# sel-driver.net
KiCad netlist of a schematic drawn in EAGLE
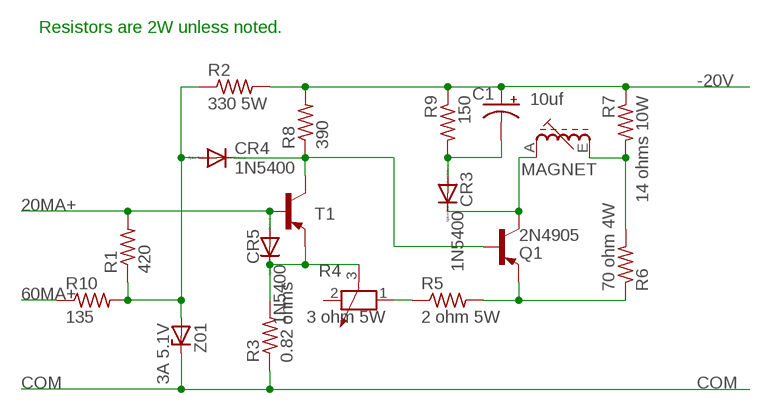
[diagram p0: schematic, sheet 1]

(export (version "E")
  (design (tool "Eeschema 10.0.6"))
  (components
    (comp (ref "C1")
      (value "10uf")
      (footprint "eagle-import:153CLV-1010")
      (libsource (lib "eagle-import") (part "CPOL-US153CLV-1010"))
    )
    (comp (ref "CR3")
      (value "1N5400")
      (footprint "eagle-import:DO201-15")
      (libsource (lib "eagle-import") (part "1N5400"))
    )
    (comp (ref "CR4")
      (value "1N5400")
      (footprint "eagle-import:DO201-15")
      (libsource (lib "eagle-import") (part "1N5400"))
    )
    (comp (ref "CR5")
      (value "1N5400")
      (footprint "eagle-import:DO201-15")
      (libsource (lib "eagle-import") (part "1N5400"))
    )
    (comp (ref "MAGNET")
      (value "71E")
      (footprint "eagle-import:71E")
      (libsource (lib "eagle-import") (part "71E"))
    )
    (comp (ref "Q1")
      (value "2N4905")
      (footprint "eagle-import:TO3")
      (libsource (lib "eagle-import") (part "2N4905"))
    )
    (comp (ref "R1")
      (value "420")
      (footprint "eagle-import:0922_22")
      (libsource (lib "eagle-import") (part "R-US_0922/22"))
    )
    (comp (ref "R2")
      (value "330 5W")
      (footprint "eagle-import:0922_22")
      (libsource (lib "eagle-import") (part "R-US_0922/22"))
    )
    (comp (ref "R3")
      (value "0.82 ohms")
      (footprint "eagle-import:0922_22")
      (libsource (lib "eagle-import") (part "R-US_0922/22"))
    )
    (comp (ref "R4")
      (value "3 ohm 5W")
      (footprint "eagle-import:PT-10")
      (libsource (lib "eagle-import") (part "POTENTIOMETER_PT-10"))
    )
    (comp (ref "R5")
      (value "2 ohm 5W")
      (footprint "eagle-import:0922_22")
      (libsource (lib "eagle-import") (part "R-US_0922/22"))
    )
    (comp (ref "R6")
      (value "70 ohm 4W")
      (footprint "eagle-import:0922_22")
      (libsource (lib "eagle-import") (part "R-US_0922/22"))
    )
    (comp (ref "R7")
      (value "14 ohms 10W")
      (footprint "eagle-import:0922_22")
      (libsource (lib "eagle-import") (part "R-US_0922/22"))
    )
    (comp (ref "R8")
      (value "390")
      (footprint "eagle-import:0922_22")
      (libsource (lib "eagle-import") (part "R-US_0922/22"))
    )
    (comp (ref "R9")
      (value "150")
      (footprint "eagle-import:0922_22")
      (libsource (lib "eagle-import") (part "R-US_0922/22"))
    )
    (comp (ref "R10")
      (value "135")
      (footprint "eagle-import:0922_22")
      (libsource (lib "eagle-import") (part "R-US_0922/22"))
    )
    (comp (ref "T1")
      (value "-PNP-TO5")
      (footprint "eagle-import:TO5")
      (libsource (lib "eagle-import") (part "-PNP-TO5"))
    )
    (comp (ref "Z01")
      (value "3A 5.1V")
      (footprint "eagle-import:C1702-15")
      (libsource (lib "eagle-import") (part "1N5333"))
    )
  )
  (nets
    (net (code "1") (name "/-20V") (class "Default")
      (node (ref "C1") (pin "+") (pinfunction "+_+") (pintype "passive"))
      (node (ref "R2") (pin "2") (pinfunction "2_2") (pintype "passive"))
      (node (ref "R7") (pin "1") (pinfunction "1_1") (pintype "passive"))
      (node (ref "R8") (pin "2") (pinfunction "2_2") (pintype "passive"))
      (node (ref "R9") (pin "1") (pinfunction "1_1") (pintype "passive"))
    )
    (net (code "2") (name "/20MA+") (class "Default")
      (node (ref "CR5") (pin "A") (pinfunction "A_A") (pintype "passive"))
      (node (ref "R1") (pin "2") (pinfunction "2_2") (pintype "passive"))
      (node (ref "T1") (pin "2") (pinfunction "B_2") (pintype "passive"))
    )
    (net (code "3") (name "/60MA+") (class "Default")
      (node (ref "R10") (pin "1") (pinfunction "1_1") (pintype "passive"))
    )
    (net (code "4") (name "/COM") (class "Default")
      (node (ref "R3") (pin "1") (pinfunction "1_1") (pintype "passive"))
      (node (ref "Z01") (pin "C") (pinfunction "C_C") (pintype "passive"))
    )
    (net (code "5") (name "Net-(C1-Pad-)") (class "Default")
      (node (ref "C1") (pin "-") (pinfunction "-_-") (pintype "passive"))
      (node (ref "CR3") (pin "A") (pinfunction "A_A") (pintype "passive"))
      (node (ref "R9") (pin "2") (pinfunction "2_2") (pintype "passive"))
    )
    (net (code "6") (name "Net-(CR3-PadC)") (class "Default")
      (node (ref "CR3") (pin "C") (pinfunction "C_C") (pintype "passive"))
      (node (ref "MAGNET") (pin "A") (pinfunction "A_A") (pintype "passive"))
      (node (ref "Q1") (pin "C") (pinfunction "C_C") (pintype "passive"))
      (node (ref "Q1") (pin "C/") (pinfunction "C_C/") (pintype "passive"))
    )
    (net (code "7") (name "Net-(CR4-PadA)") (class "Default")
      (node (ref "CR4") (pin "A") (pinfunction "A_A") (pintype "passive"))
      (node (ref "R1") (pin "1") (pinfunction "1_1") (pintype "passive"))
      (node (ref "R10") (pin "2") (pinfunction "2_2") (pintype "passive"))
      (node (ref "R2") (pin "1") (pinfunction "1_1") (pintype "passive"))
      (node (ref "Z01") (pin "A") (pinfunction "A_A") (pintype "passive"))
    )
    (net (code "8") (name "Net-(MAGNET-PadE)") (class "Default")
      (node (ref "MAGNET") (pin "E") (pinfunction "E_E") (pintype "passive"))
      (node (ref "R6") (pin "2") (pinfunction "2_2") (pintype "passive"))
      (node (ref "R7") (pin "2") (pinfunction "2_2") (pintype "passive"))
    )
    (net (code "9") (name "Net-(Q1-PadE)") (class "Default")
      (node (ref "Q1") (pin "E") (pinfunction "E_E") (pintype "passive"))
      (node (ref "R5") (pin "2") (pinfunction "2_2") (pintype "passive"))
      (node (ref "R6") (pin "1") (pinfunction "1_1") (pintype "passive"))
    )
    (net (code "10") (name "Net-(R4-Pad1)") (class "Default")
      (node (ref "R4") (pin "1") (pinfunction "1_1") (pintype "passive"))
      (node (ref "R5") (pin "1") (pinfunction "1_1") (pintype "passive"))
    )
    (net (code "11") (name "Net-(T1-C)") (class "Default")
      (node (ref "CR4") (pin "C") (pinfunction "C_C") (pintype "passive"))
      (node (ref "Q1") (pin "B") (pinfunction "B_B") (pintype "passive"))
      (node (ref "R8") (pin "1") (pinfunction "1_1") (pintype "passive"))
      (node (ref "T1") (pin "3") (pinfunction "C_3") (pintype "passive"))
    )
    (net (code "12") (name "Net-(T1-E)") (class "Default")
      (node (ref "CR5") (pin "C") (pinfunction "C_C") (pintype "passive"))
      (node (ref "R3") (pin "2") (pinfunction "2_2") (pintype "passive"))
      (node (ref "R4") (pin "3") (pinfunction "3_3") (pintype "passive"))
      (node (ref "T1") (pin "1") (pinfunction "E_1") (pintype "passive"))
    )
    (net (code "13") (name "unconnected-(R4-Pad2)") (class "Default")
      (node (ref "R4") (pin "2") (pinfunction "2_2") (pintype "passive"))
    )
  )
)
